# pm2016.net
KiCad netlist of a schematic drawn in EAGLE
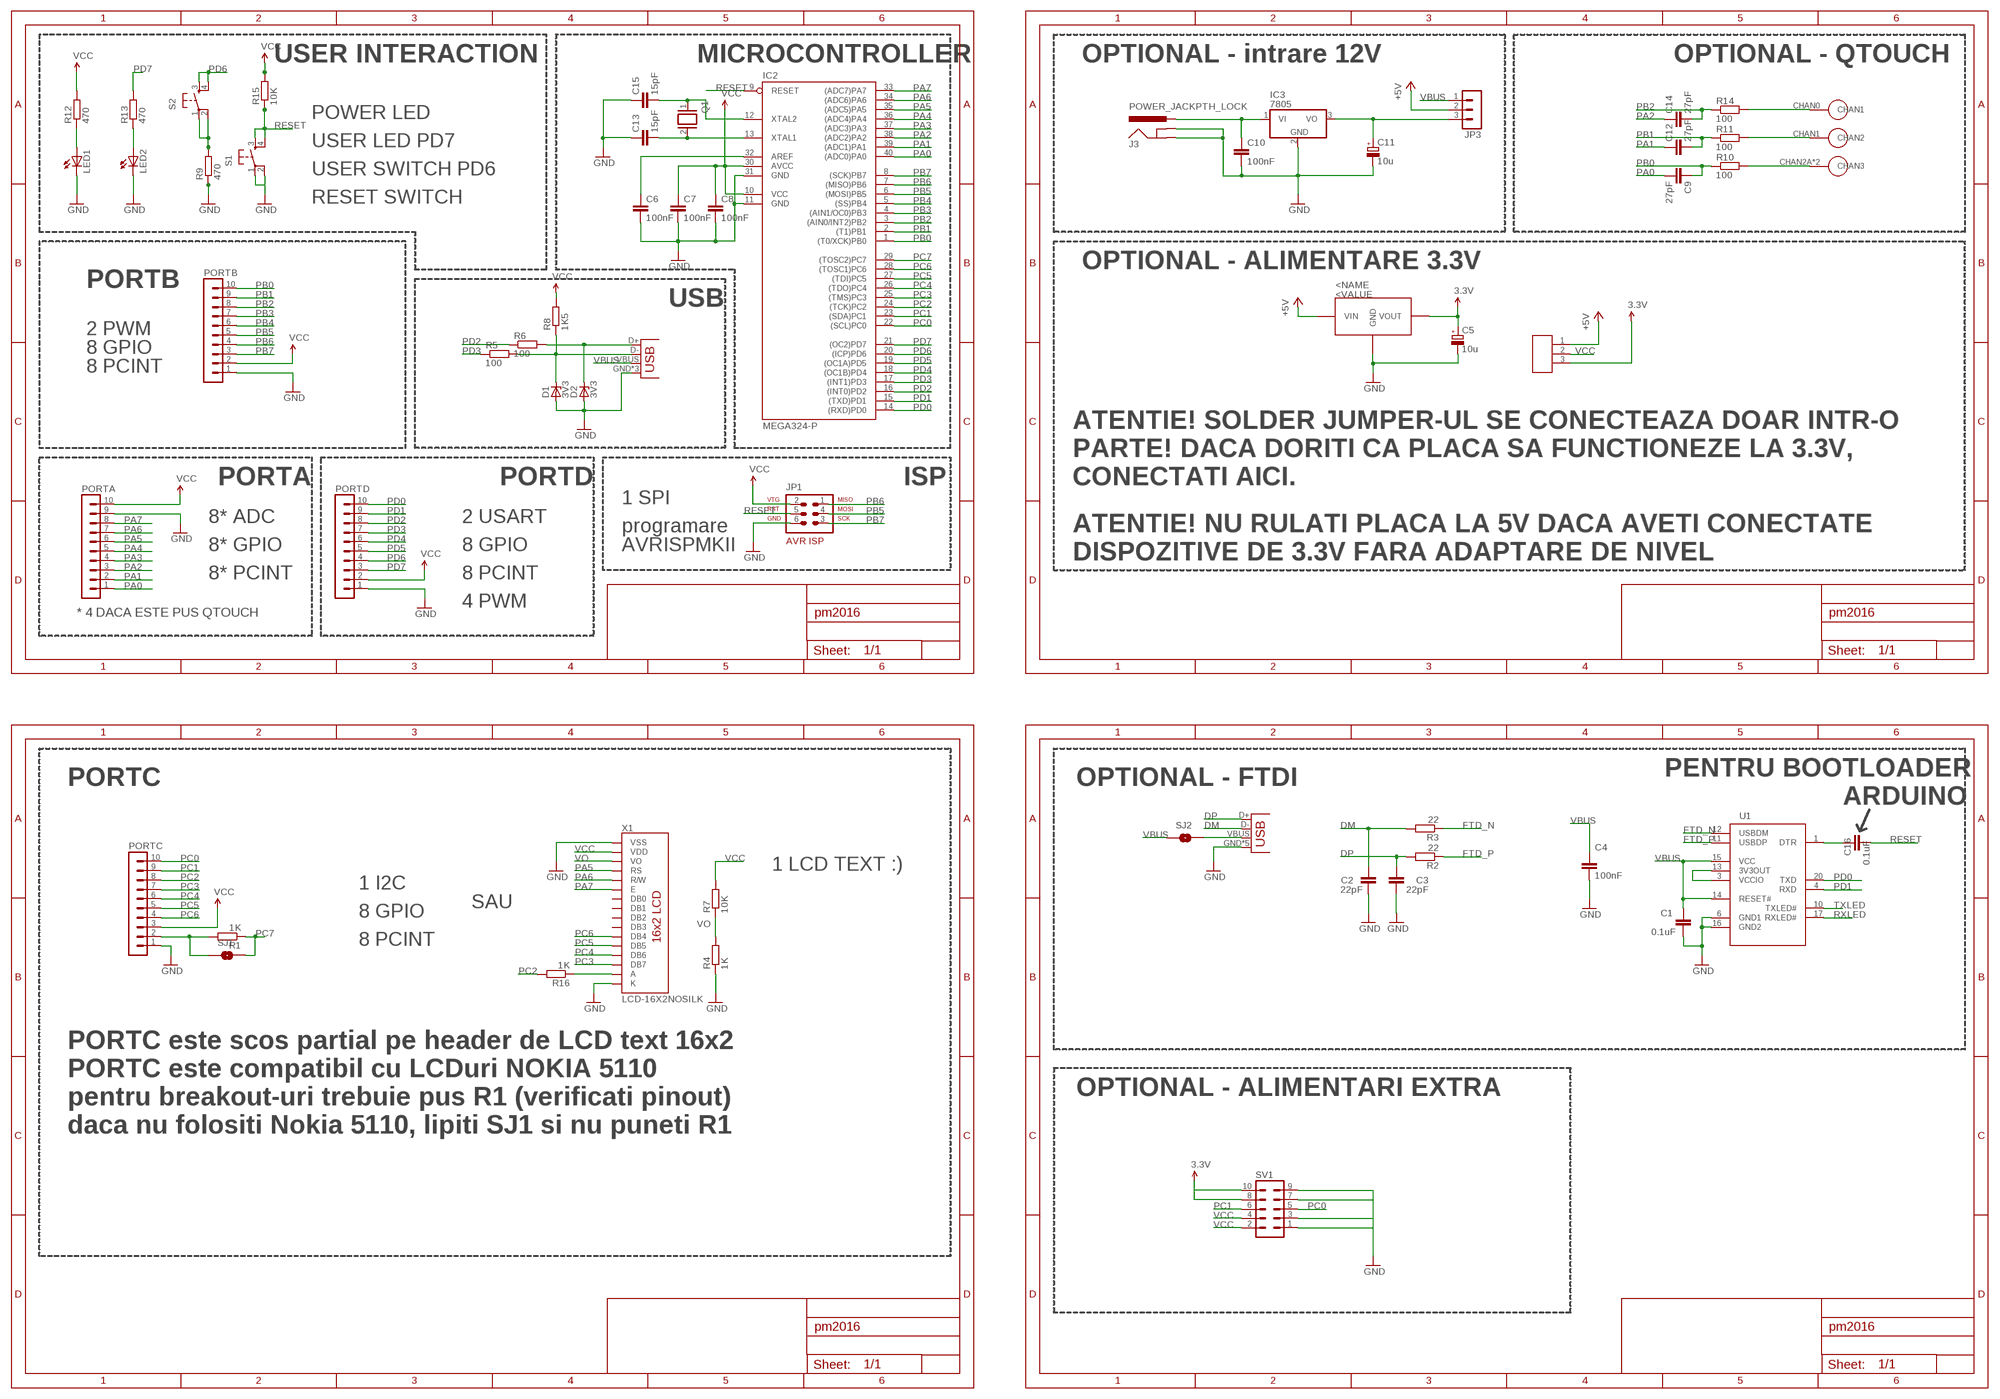
[diagram p0: schematic, sheet 1]

(export (version "E")
  (design (tool "Eeschema 10.0.6"))
  (components
    (comp (ref "C1")
      (value "0.1uF")
      (footprint "eagle-import:C0603")
      (libsource (lib "eagle-import") (part "C-EUC0603"))
    )
    (comp (ref "C2")
      (value "22pF")
      (footprint "eagle-import:C0603")
      (libsource (lib "eagle-import") (part "C-EUC0603"))
    )
    (comp (ref "C3")
      (value "22pF")
      (footprint "eagle-import:C0603")
      (libsource (lib "eagle-import") (part "C-EUC0603"))
    )
    (comp (ref "C4")
      (value "100nF")
      (footprint "eagle-import:C0603")
      (libsource (lib "eagle-import") (part "C-EUC0603"))
    )
    (comp (ref "C5")
      (value "10u")
      (footprint "eagle-import:E2,5-5")
      (libsource (lib "eagle-import") (part "CPOL-EUE2.5-5"))
    )
    (comp (ref "C6")
      (value "100nF")
      (footprint "eagle-import:C025-025X050")
      (libsource (lib "eagle-import") (part "C-EUC_PM"))
    )
    (comp (ref "C7")
      (value "100nF")
      (footprint "eagle-import:C025-025X050")
      (libsource (lib "eagle-import") (part "C-EUC_PM"))
    )
    (comp (ref "C8")
      (value "100nF")
      (footprint "eagle-import:C025-025X050")
      (libsource (lib "eagle-import") (part "C-EUC_PM"))
    )
    (comp (ref "C9")
      (value "27pF")
      (footprint "eagle-import:C1206")
      (libsource (lib "eagle-import") (part "C-EUC1206"))
    )
    (comp (ref "C10")
      (value "100nF")
      (footprint "eagle-import:C025-025X050@1")
      (libsource (lib "eagle-import") (part "C-EU025-025X050"))
    )
    (comp (ref "C11")
      (value "10u")
      (footprint "eagle-import:E2,5-5")
      (libsource (lib "eagle-import") (part "CPOL-EUE2.5-5"))
    )
    (comp (ref "C12")
      (value "27pF")
      (footprint "eagle-import:C1206")
      (libsource (lib "eagle-import") (part "C-EUC1206"))
    )
    (comp (ref "C13")
      (value "15pF")
      (footprint "eagle-import:C025-025X050")
      (libsource (lib "eagle-import") (part "C-EUC_PM"))
    )
    (comp (ref "C14")
      (value "27pF")
      (footprint "eagle-import:C1206")
      (libsource (lib "eagle-import") (part "C-EUC1206"))
    )
    (comp (ref "C15")
      (value "15pF")
      (footprint "eagle-import:C025-025X050")
      (libsource (lib "eagle-import") (part "C-EUC_PM"))
    )
    (comp (ref "C16")
      (value "0.1uF")
      (footprint "eagle-import:C0603")
      (libsource (lib "eagle-import") (part "C-EUC0603"))
    )
    (comp (ref "D1")
      (value "3V3")
      (footprint "eagle-import:DO34Z7")
      (libsource (lib "eagle-import") (part "ZENER-DIODEDO34-7"))
    )
    (comp (ref "D2")
      (value "3V3")
      (footprint "eagle-import:DO34Z7")
      (libsource (lib "eagle-import") (part "ZENER-DIODEDO34-7"))
    )
    (comp (ref "IC1")
      (value "LE33")
      (footprint "eagle-import:TO92")
      (libsource (lib "eagle-import") (part "LE33"))
    )
    (comp (ref "IC2")
      (value "MEGA324-P")
      (footprint "eagle-import:DIL40")
      (fields (field (name "MPN") "ATMEGA16-16PU"))
      (libsource (lib "eagle-import") (part "MEGA16-P"))
    )
    (comp (ref "IC3")
      (value "7805")
      (footprint "eagle-import:TO22H_NOHOLE")
      (libsource (lib "eagle-import") (part "78TNH05"))
    )
    (comp (ref "J1")
      (value "USB")
      (footprint "eagle-import:ZX62D-B-5PA8")
      (libsource (lib "eagle-import") (part "USB"))
    )
    (comp (ref "J2")
      (value "USBPTH")
      (footprint "eagle-import:USB-B-PTH")
      (libsource (lib "eagle-import") (part "USBPTH"))
    )
    (comp (ref "J3")
      (value "POWER_JACKPTH_LOCK")
      (footprint "eagle-import:POWER_JACK_PTH_LOCK")
      (libsource (lib "eagle-import") (part "POWER_JACKPTH_LOCK"))
    )
    (comp (ref "JP1")
      (value "AVR-ISP-6")
      (footprint "eagle-import:AVR-ISP-6")
      (libsource (lib "eagle-import") (part "AVR-ISP-6"))
    )
    (comp (ref "JP2")
      (value "SJUMPER")
      (footprint "eagle-import:SJUMPER_PACK")
      (libsource (lib "eagle-import") (part "SJUMPER"))
    )
    (comp (ref "JP3")
      (value "MA03-1")
      (footprint "eagle-import:MA03-1")
      (libsource (lib "eagle-import") (part "MA03-1"))
    )
    (comp (ref "LED1")
      (value "LED5MM")
      (footprint "eagle-import:LED5MM")
      (libsource (lib "eagle-import") (part "LED5MM"))
    )
    (comp (ref "LED2")
      (value "LED5MM")
      (footprint "eagle-import:LED5MM")
      (libsource (lib "eagle-import") (part "LED5MM"))
    )
    (comp (ref "PORTA")
      (value "MA10-1")
      (footprint "eagle-import:MA10-1")
      (libsource (lib "eagle-import") (part "MA10-1"))
    )
    (comp (ref "PORTB")
      (value "MA10-1")
      (footprint "eagle-import:MA10-1")
      (libsource (lib "eagle-import") (part "MA10-1"))
    )
    (comp (ref "PORTC")
      (value "MA10-1")
      (footprint "eagle-import:MA10-1")
      (libsource (lib "eagle-import") (part "MA10-1"))
    )
    (comp (ref "PORTD")
      (value "MA10-1")
      (footprint "eagle-import:MA10-1")
      (libsource (lib "eagle-import") (part "MA10-1"))
    )
    (comp (ref "Q1")
      (value "XTAL/S")
      (footprint "eagle-import:QS")
      (libsource (lib "eagle-import") (part "XTAL/S"))
    )
    (comp (ref "R1")
      (value "1K")
      (footprint "eagle-import:0204_7")
      (libsource (lib "eagle-import") (part "R-EU_0204/7"))
    )
    (comp (ref "R2")
      (value "22")
      (footprint "eagle-import:R0603")
      (libsource (lib "eagle-import") (part "resistor_R-EU_R0603"))
    )
    (comp (ref "R3")
      (value "22")
      (footprint "eagle-import:R0603")
      (libsource (lib "eagle-import") (part "resistor_R-EU_R0603"))
    )
    (comp (ref "R4")
      (value "1K")
      (footprint "eagle-import:0204_7")
      (libsource (lib "eagle-import") (part "R-EU_0204/7"))
    )
    (comp (ref "R5")
      (value "100")
      (footprint "eagle-import:0204_7")
      (libsource (lib "eagle-import") (part "R-EU_0204/7"))
    )
    (comp (ref "R6")
      (value "100")
      (footprint "eagle-import:0204_7")
      (libsource (lib "eagle-import") (part "R-EU_0204/7"))
    )
    (comp (ref "R7")
      (value "10K")
      (footprint "eagle-import:0204_7")
      (libsource (lib "eagle-import") (part "R-EU_0204/7"))
    )
    (comp (ref "R8")
      (value "1K5")
      (footprint "eagle-import:0204_7")
      (libsource (lib "eagle-import") (part "R-EU_0204/7"))
    )
    (comp (ref "R9")
      (value "470")
      (footprint "eagle-import:0204_7")
      (libsource (lib "eagle-import") (part "R-EU_0204/7"))
    )
    (comp (ref "R10")
      (value "100")
      (footprint "eagle-import:M1206")
      (libsource (lib "eagle-import") (part "resistor_R-EU_M1206"))
    )
    (comp (ref "R11")
      (value "100")
      (footprint "eagle-import:M1206")
      (libsource (lib "eagle-import") (part "resistor_R-EU_M1206"))
    )
    (comp (ref "R12")
      (value "470")
      (footprint "eagle-import:0204_7")
      (libsource (lib "eagle-import") (part "R-EU_0204/7"))
    )
    (comp (ref "R13")
      (value "470")
      (footprint "eagle-import:0204_7")
      (libsource (lib "eagle-import") (part "R-EU_0204/7"))
    )
    (comp (ref "R14")
      (value "100")
      (footprint "eagle-import:M1206")
      (libsource (lib "eagle-import") (part "resistor_R-EU_M1206"))
    )
    (comp (ref "R15")
      (value "10K")
      (footprint "eagle-import:0204_7")
      (libsource (lib "eagle-import") (part "R-EU_0204/7"))
    )
    (comp (ref "R16")
      (value "1K")
      (footprint "eagle-import:0204_7")
      (libsource (lib "eagle-import") (part "R-EU_0204/7"))
    )
    (comp (ref "S1")
      (value "TAC_SWITCHPTH")
      (footprint "eagle-import:TACTILE-PTH")
      (libsource (lib "eagle-import") (part "TAC_SWITCHPTH"))
    )
    (comp (ref "S2")
      (value "TAC_SWITCHPTH")
      (footprint "eagle-import:TACTILE-PTH")
      (libsource (lib "eagle-import") (part "TAC_SWITCHPTH"))
    )
    (comp (ref "SJ1")
      (value "SOLDERJUMPERNC")
      (footprint "eagle-import:SJ-NC")
      (libsource (lib "eagle-import") (part "SOLDERJUMPERNC"))
    )
    (comp (ref "SJ2")
      (value "SOLDERJUMPERNC")
      (footprint "eagle-import:SJ-NC")
      (libsource (lib "eagle-import") (part "SOLDERJUMPERNC"))
    )
    (comp (ref "SV1")
      (value "MA05-2")
      (footprint "eagle-import:MA05-2")
      (libsource (lib "eagle-import") (part "MA05-2"))
    )
    (comp (ref "U$1")
      (value "QT_SLIDER")
      (footprint "eagle-import:QT_SLIDER")
      (libsource (lib "eagle-import") (part "QT_SLIDER"))
    )
    (comp (ref "U1")
      (value "FT231XS")
      (footprint "eagle-import:SSOP20")
      (libsource (lib "eagle-import") (part "FT231XS"))
    )
    (comp (ref "X1")
      (value "LCD-16X2NOSILK")
      (footprint "eagle-import:LCD-16X2_NOSILK")
      (libsource (lib "eagle-import") (part "LCD-16X2NOSILK"))
    )
  )
  (nets
    (net (code "1") (name "+5V") (class "Default")
      (node (ref "IC1") (pin "3") (pinfunction "VIN_3") (pintype "bidirectional"))
      (node (ref "JP2") (pin "1") (pinfunction "P$1_1") (pintype "bidirectional"))
      (node (ref "JP3") (pin "2") (pinfunction "2_2") (pintype "passive"))
    )
    (net (code "2") (name "/DM") (class "Default")
      (node (ref "C2") (pin "2") (pinfunction "2_2") (pintype "passive"))
      (node (ref "J1") (pin "D-") (pinfunction "D-_D-") (pintype "bidirectional"))
      (node (ref "R3") (pin "2") (pinfunction "2_2") (pintype "passive"))
    )
    (net (code "3") (name "/DP") (class "Default")
      (node (ref "C3") (pin "2") (pinfunction "2_2") (pintype "passive"))
      (node (ref "J1") (pin "D+") (pinfunction "D+_D+") (pintype "bidirectional"))
      (node (ref "R2") (pin "2") (pinfunction "2_2") (pintype "passive"))
    )
    (net (code "4") (name "/FTD_N") (class "Default")
      (node (ref "R3") (pin "1") (pinfunction "1_1") (pintype "passive"))
      (node (ref "U1") (pin "12") (pinfunction "USBDM_12") (pintype "bidirectional"))
    )
    (net (code "5") (name "/FTD_P") (class "Default")
      (node (ref "R2") (pin "1") (pinfunction "1_1") (pintype "passive"))
      (node (ref "U1") (pin "11") (pinfunction "USBDP_11") (pintype "bidirectional"))
    )
    (net (code "6") (name "/PA0") (class "Default")
      (node (ref "C9") (pin "2") (pinfunction "2_2") (pintype "passive"))
      (node (ref "IC2") (pin "40") (pinfunction "(ADC0)PA0_40") (pintype "bidirectional"))
      (node (ref "PORTA") (pin "1") (pinfunction "1_1") (pintype "passive"))
    )
    (net (code "7") (name "/PA1") (class "Default")
      (node (ref "C12") (pin "1") (pinfunction "1_1") (pintype "passive"))
      (node (ref "IC2") (pin "39") (pinfunction "(ADC1)PA1_39") (pintype "bidirectional"))
      (node (ref "PORTA") (pin "2") (pinfunction "2_2") (pintype "passive"))
    )
    (net (code "8") (name "/PA2") (class "Default")
      (node (ref "C14") (pin "1") (pinfunction "1_1") (pintype "passive"))
      (node (ref "IC2") (pin "38") (pinfunction "(ADC2)PA2_38") (pintype "bidirectional"))
      (node (ref "PORTA") (pin "3") (pinfunction "3_3") (pintype "passive"))
    )
    (net (code "9") (name "/PA3") (class "Default")
      (node (ref "IC2") (pin "37") (pinfunction "(ADC3)PA3_37") (pintype "bidirectional"))
      (node (ref "PORTA") (pin "4") (pinfunction "4_4") (pintype "passive"))
    )
    (net (code "10") (name "/PA4") (class "Default")
      (node (ref "IC2") (pin "36") (pinfunction "(ADC4)PA4_36") (pintype "bidirectional"))
      (node (ref "PORTA") (pin "5") (pinfunction "5_5") (pintype "passive"))
    )
    (net (code "11") (name "/PA5") (class "Default")
      (node (ref "IC2") (pin "35") (pinfunction "(ADC5)PA5_35") (pintype "bidirectional"))
      (node (ref "PORTA") (pin "6") (pinfunction "6_6") (pintype "passive"))
      (node (ref "X1") (pin "4") (pinfunction "RS_4") (pintype "input"))
    )
    (net (code "12") (name "/PA6") (class "Default")
      (node (ref "IC2") (pin "34") (pinfunction "(ADC6)PA6_34") (pintype "bidirectional"))
      (node (ref "PORTA") (pin "7") (pinfunction "7_7") (pintype "passive"))
      (node (ref "X1") (pin "5") (pinfunction "R/W_5") (pintype "input"))
    )
    (net (code "13") (name "/PA7") (class "Default")
      (node (ref "IC2") (pin "33") (pinfunction "(ADC7)PA7_33") (pintype "bidirectional"))
      (node (ref "PORTA") (pin "8") (pinfunction "8_8") (pintype "passive"))
      (node (ref "X1") (pin "6") (pinfunction "E_6") (pintype "input"))
    )
    (net (code "14") (name "/PB0") (class "Default")
      (node (ref "C9") (pin "1") (pinfunction "1_1") (pintype "passive"))
      (node (ref "IC2") (pin "1") (pinfunction "(T0/XCK)PB0_1") (pintype "bidirectional"))
      (node (ref "PORTB") (pin "10") (pinfunction "10_10") (pintype "passive"))
      (node (ref "R10") (pin "1") (pinfunction "1_1") (pintype "passive"))
    )
    (net (code "15") (name "/PB1") (class "Default")
      (node (ref "C12") (pin "2") (pinfunction "2_2") (pintype "passive"))
      (node (ref "IC2") (pin "2") (pinfunction "(T1)PB1_2") (pintype "bidirectional"))
      (node (ref "PORTB") (pin "9") (pinfunction "9_9") (pintype "passive"))
      (node (ref "R11") (pin "1") (pinfunction "1_1") (pintype "passive"))
    )
    (net (code "16") (name "/PB2") (class "Default")
      (node (ref "C14") (pin "2") (pinfunction "2_2") (pintype "passive"))
      (node (ref "IC2") (pin "3") (pinfunction "(AIN0/INT2)PB2_3") (pintype "bidirectional"))
      (node (ref "PORTB") (pin "8") (pinfunction "8_8") (pintype "passive"))
      (node (ref "R14") (pin "1") (pinfunction "1_1") (pintype "passive"))
    )
    (net (code "17") (name "/PB3") (class "Default")
      (node (ref "IC2") (pin "4") (pinfunction "(AIN1/OC0)PB3_4") (pintype "bidirectional"))
      (node (ref "PORTB") (pin "7") (pinfunction "7_7") (pintype "passive"))
    )
    (net (code "18") (name "/PB4") (class "Default")
      (node (ref "IC2") (pin "5") (pinfunction "(SS)PB4_5") (pintype "bidirectional"))
      (node (ref "PORTB") (pin "6") (pinfunction "6_6") (pintype "passive"))
    )
    (net (code "19") (name "/PB5") (class "Default")
      (node (ref "IC2") (pin "6") (pinfunction "(MOSI)PB5_6") (pintype "bidirectional"))
      (node (ref "JP1") (pin "4") (pinfunction "4_4") (pintype "passive"))
      (node (ref "PORTB") (pin "5") (pinfunction "5_5") (pintype "passive"))
    )
    (net (code "20") (name "/PB6") (class "Default")
      (node (ref "IC2") (pin "7") (pinfunction "(MISO)PB6_7") (pintype "bidirectional"))
      (node (ref "JP1") (pin "1") (pinfunction "1_1") (pintype "passive"))
      (node (ref "PORTB") (pin "4") (pinfunction "4_4") (pintype "passive"))
    )
    (net (code "21") (name "/PB7") (class "Default")
      (node (ref "IC2") (pin "8") (pinfunction "(SCK)PB7_8") (pintype "bidirectional"))
      (node (ref "JP1") (pin "3") (pinfunction "3_3") (pintype "passive"))
      (node (ref "PORTB") (pin "3") (pinfunction "3_3") (pintype "passive"))
    )
    (net (code "22") (name "/PC0") (class "Default")
      (node (ref "IC2") (pin "22") (pinfunction "(SCL)PC0_22") (pintype "bidirectional"))
      (node (ref "PORTC") (pin "10") (pinfunction "10_10") (pintype "passive"))
      (node (ref "SV1") (pin "5") (pinfunction "5_5") (pintype "passive"))
    )
    (net (code "23") (name "/PC1") (class "Default")
      (node (ref "IC2") (pin "23") (pinfunction "(SDA)PC1_23") (pintype "bidirectional"))
      (node (ref "PORTC") (pin "9") (pinfunction "9_9") (pintype "passive"))
      (node (ref "SV1") (pin "6") (pinfunction "6_6") (pintype "passive"))
    )
    (net (code "24") (name "/PC2") (class "Default")
      (node (ref "IC2") (pin "24") (pinfunction "(TCK)PC2_24") (pintype "bidirectional"))
      (node (ref "PORTC") (pin "8") (pinfunction "8_8") (pintype "passive"))
      (node (ref "R16") (pin "2") (pinfunction "2_2") (pintype "passive"))
    )
    (net (code "25") (name "/PC3") (class "Default")
      (node (ref "IC2") (pin "25") (pinfunction "(TMS)PC3_25") (pintype "bidirectional"))
      (node (ref "PORTC") (pin "7") (pinfunction "7_7") (pintype "passive"))
      (node (ref "X1") (pin "14") (pinfunction "DB7_14") (pintype "bidirectional"))
    )
    (net (code "26") (name "/PC4") (class "Default")
      (node (ref "IC2") (pin "26") (pinfunction "(TDO)PC4_26") (pintype "bidirectional"))
      (node (ref "PORTC") (pin "6") (pinfunction "6_6") (pintype "passive"))
      (node (ref "X1") (pin "13") (pinfunction "DB6_13") (pintype "bidirectional"))
    )
    (net (code "27") (name "/PC5") (class "Default")
      (node (ref "IC2") (pin "27") (pinfunction "(TDI)PC5_27") (pintype "bidirectional"))
      (node (ref "PORTC") (pin "5") (pinfunction "5_5") (pintype "passive"))
      (node (ref "X1") (pin "12") (pinfunction "DB5_12") (pintype "bidirectional"))
    )
    (net (code "28") (name "/PC6") (class "Default")
      (node (ref "IC2") (pin "28") (pinfunction "(TOSC1)PC6_28") (pintype "bidirectional"))
      (node (ref "PORTC") (pin "4") (pinfunction "4_4") (pintype "passive"))
      (node (ref "X1") (pin "11") (pinfunction "DB4_11") (pintype "bidirectional"))
    )
    (net (code "29") (name "/PC7") (class "Default")
      (node (ref "IC2") (pin "29") (pinfunction "(TOSC2)PC7_29") (pintype "bidirectional"))
      (node (ref "R1") (pin "1") (pinfunction "1_1") (pintype "passive"))
      (node (ref "SJ1") (pin "2") (pinfunction "2_2") (pintype "passive"))
    )
    (net (code "30") (name "/PD0") (class "Default")
      (node (ref "IC2") (pin "14") (pinfunction "(RXD)PD0_14") (pintype "bidirectional"))
      (node (ref "PORTD") (pin "10") (pinfunction "10_10") (pintype "passive"))
      (node (ref "U1") (pin "20") (pinfunction "TXD_20") (pintype "output"))
    )
    (net (code "31") (name "/PD1") (class "Default")
      (node (ref "IC2") (pin "15") (pinfunction "(TXD)PD1_15") (pintype "bidirectional"))
      (node (ref "PORTD") (pin "9") (pinfunction "9_9") (pintype "passive"))
      (node (ref "U1") (pin "4") (pinfunction "RXD_4") (pintype "input"))
    )
    (net (code "32") (name "/PD2") (class "Default")
      (node (ref "IC2") (pin "16") (pinfunction "(INT0)PD2_16") (pintype "bidirectional"))
      (node (ref "PORTD") (pin "8") (pinfunction "8_8") (pintype "passive"))
      (node (ref "R6") (pin "1") (pinfunction "1_1") (pintype "passive"))
    )
    (net (code "33") (name "/PD3") (class "Default")
      (node (ref "IC2") (pin "17") (pinfunction "(INT1)PD3_17") (pintype "bidirectional"))
      (node (ref "PORTD") (pin "7") (pinfunction "7_7") (pintype "passive"))
      (node (ref "R5") (pin "1") (pinfunction "1_1") (pintype "passive"))
    )
    (net (code "34") (name "/PD4") (class "Default")
      (node (ref "IC2") (pin "18") (pinfunction "(OC1B)PD4_18") (pintype "bidirectional"))
      (node (ref "PORTD") (pin "6") (pinfunction "6_6") (pintype "passive"))
    )
    (net (code "35") (name "/PD5") (class "Default")
      (node (ref "IC2") (pin "19") (pinfunction "(OC1A)PD5_19") (pintype "bidirectional"))
      (node (ref "PORTD") (pin "5") (pinfunction "5_5") (pintype "passive"))
    )
    (net (code "36") (name "/PD6") (class "Default")
      (node (ref "IC2") (pin "20") (pinfunction "(ICP)PD6_20") (pintype "bidirectional"))
      (node (ref "PORTD") (pin "4") (pinfunction "4_4") (pintype "passive"))
      (node (ref "S2") (pin "3") (pinfunction "3_3") (pintype "passive"))
      (node (ref "S2") (pin "4") (pinfunction "4_4") (pintype "passive"))
    )
    (net (code "37") (name "/PD7") (class "Default")
      (node (ref "IC2") (pin "21") (pinfunction "(OC2)PD7_21") (pintype "bidirectional"))
      (node (ref "PORTD") (pin "3") (pinfunction "3_3") (pintype "passive"))
      (node (ref "R13") (pin "2") (pinfunction "2_2") (pintype "passive"))
    )
    (net (code "38") (name "/RESET") (class "Default")
      (node (ref "C16") (pin "2") (pinfunction "2_2") (pintype "passive"))
      (node (ref "IC2") (pin "9") (pinfunction "RESET_9") (pintype "input"))
      (node (ref "JP1") (pin "5") (pinfunction "5_5") (pintype "passive"))
      (node (ref "R15") (pin "1") (pinfunction "1_1") (pintype "passive"))
      (node (ref "S1") (pin "3") (pinfunction "3_3") (pintype "passive"))
      (node (ref "S1") (pin "4") (pinfunction "4_4") (pintype "passive"))
    )
    (net (code "39") (name "/RXLED") (class "Default")
      (node (ref "U1") (pin "17") (pinfunction "RXLED#_17") (pintype "output"))
    )
    (net (code "40") (name "/TXLED") (class "Default")
      (node (ref "U1") (pin "10") (pinfunction "TXLED#_10") (pintype "output"))
    )
    (net (code "41") (name "/VBUS") (class "Default")
      (node (ref "C1") (pin "1") (pinfunction "1_1") (pintype "passive"))
      (node (ref "C4") (pin "1") (pinfunction "1_1") (pintype "passive"))
      (node (ref "J2") (pin "VBUS") (pinfunction "VBUS_VBUS") (pintype "bidirectional"))
      (node (ref "JP3") (pin "1") (pinfunction "1_1") (pintype "passive"))
      (node (ref "SJ2") (pin "1") (pinfunction "1_1") (pintype "passive"))
      (node (ref "U1") (pin "14") (pinfunction "RESET#_14") (pintype "input"))
      (node (ref "U1") (pin "15") (pinfunction "VCC_15") (pintype "power_in"))
    )
    (net (code "42") (name "/VO") (class "Default")
      (node (ref "R4") (pin "2") (pinfunction "2_2") (pintype "passive"))
      (node (ref "R7") (pin "1") (pinfunction "1_1") (pintype "passive"))
      (node (ref "X1") (pin "3") (pinfunction "VO_3") (pintype "bidirectional"))
    )
    (net (code "43") (name "3.3V") (class "Default")
      (node (ref "C5") (pin "+") (pinfunction "+_+") (pintype "passive"))
      (node (ref "IC1") (pin "1") (pinfunction "VOUT_1") (pintype "bidirectional"))
      (node (ref "JP2") (pin "3") (pinfunction "P$3_3") (pintype "bidirectional"))
      (node (ref "SV1") (pin "10") (pinfunction "10_10") (pintype "passive"))
      (node (ref "SV1") (pin "8") (pinfunction "8_8") (pintype "passive"))
    )
    (net (code "44") (name "GND") (class "Default")
      (node (ref "C1") (pin "2") (pinfunction "2_2") (pintype "passive"))
      (node (ref "C10") (pin "2") (pinfunction "2_2") (pintype "passive"))
      (node (ref "C11") (pin "-") (pinfunction "-_-") (pintype "passive"))
      (node (ref "C13") (pin "1") (pinfunction "1_1") (pintype "passive"))
      (node (ref "C15") (pin "1") (pinfunction "1_1") (pintype "passive"))
      (node (ref "C2") (pin "1") (pinfunction "1_1") (pintype "passive"))
      (node (ref "C3") (pin "1") (pinfunction "1_1") (pintype "passive"))
      (node (ref "C4") (pin "2") (pinfunction "2_2") (pintype "passive"))
      (node (ref "C5") (pin "-") (pinfunction "-_-") (pintype "passive"))
      (node (ref "C6") (pin "2") (pinfunction "2_2") (pintype "passive"))
      (node (ref "C7") (pin "2") (pinfunction "2_2") (pintype "passive"))
      (node (ref "C8") (pin "2") (pinfunction "2_2") (pintype "passive"))
      (node (ref "D1") (pin "A") (pinfunction "A_A") (pintype "passive"))
      (node (ref "D2") (pin "A") (pinfunction "A_A") (pintype "passive"))
      (node (ref "IC1") (pin "2") (pinfunction "GND_2") (pintype "bidirectional"))
      (node (ref "IC2") (pin "11") (pinfunction "GND_11") (pintype "power_in"))
      (node (ref "IC2") (pin "31") (pinfunction "GND_31") (pintype "power_in"))
      (node (ref "IC3") (pin "2") (pinfunction "GND_2") (pintype "passive"))
      (node (ref "J1") (pin "GND") (pinfunction "GND_GND") (pintype "bidirectional"))
      (node (ref "J1") (pin "P$10") (pinfunction "GND_P$10") (pintype "bidirectional"))
      (node (ref "J1") (pin "P$11") (pinfunction "GND_P$11") (pintype "bidirectional"))
      (node (ref "J1") (pin "P$8") (pinfunction "GND_P$8") (pintype "bidirectional"))
      (node (ref "J1") (pin "P$9") (pinfunction "GND_P$9") (pintype "bidirectional"))
      (node (ref "J2") (pin "GND") (pinfunction "GND_GND") (pintype "bidirectional"))
      (node (ref "J2") (pin "P$1") (pinfunction "GND_P$1") (pintype "bidirectional"))
      (node (ref "J2") (pin "P$2") (pinfunction "GND_P$2") (pintype "bidirectional"))
      (node (ref "J3") (pin "GND") (pinfunction "GND_GND") (pintype "bidirectional"))
      (node (ref "J3") (pin "GNDBREAK") (pinfunction "GNDBREAK_GNDBREAK") (pintype "bidirectional"))
      (node (ref "JP1") (pin "6") (pinfunction "6_6") (pintype "passive"))
      (node (ref "LED1") (pin "K") (pinfunction "C_K") (pintype "passive"))
      (node (ref "LED2") (pin "K") (pinfunction "C_K") (pintype "passive"))
      (node (ref "PORTA") (pin "9") (pinfunction "9_9") (pintype "passive"))
      (node (ref "PORTB") (pin "1") (pinfunction "1_1") (pintype "passive"))
      (node (ref "PORTC") (pin "1") (pinfunction "1_1") (pintype "passive"))
      (node (ref "PORTD") (pin "1") (pinfunction "1_1") (pintype "passive"))
      (node (ref "R4") (pin "1") (pinfunction "1_1") (pintype "passive"))
      (node (ref "R9") (pin "1") (pinfunction "1_1") (pintype "passive"))
      (node (ref "S1") (pin "1") (pinfunction "1_1") (pintype "passive"))
      (node (ref "S1") (pin "2") (pinfunction "2_2") (pintype "passive"))
      (node (ref "SV1") (pin "1") (pinfunction "1_1") (pintype "passive"))
      (node (ref "SV1") (pin "3") (pinfunction "3_3") (pintype "passive"))
      (node (ref "SV1") (pin "7") (pinfunction "7_7") (pintype "passive"))
      (node (ref "SV1") (pin "9") (pinfunction "9_9") (pintype "passive"))
      (node (ref "U1") (pin "16") (pinfunction "GND2_16") (pintype "power_in"))
      (node (ref "U1") (pin "6") (pinfunction "GND1_6") (pintype "power_in"))
      (node (ref "X1") (pin "1") (pinfunction "VSS_1") (pintype "power_in"))
      (node (ref "X1") (pin "16") (pinfunction "K_16") (pintype "power_in"))
    )
    (net (code "45") (name "Net-(D1-PadC)") (class "Default")
      (node (ref "D1") (pin "C") (pinfunction "C_C") (pintype "passive"))
      (node (ref "J2") (pin "D-") (pinfunction "D-_D-") (pintype "bidirectional"))
      (node (ref "R5") (pin "2") (pinfunction "2_2") (pintype "passive"))
      (node (ref "R8") (pin "1") (pinfunction "1_1") (pintype "passive"))
    )
    (net (code "46") (name "Net-(D2-PadC)") (class "Default")
      (node (ref "D2") (pin "C") (pinfunction "C_C") (pintype "passive"))
      (node (ref "J2") (pin "D+") (pinfunction "D+_D+") (pintype "bidirectional"))
      (node (ref "R6") (pin "2") (pinfunction "2_2") (pintype "passive"))
    )
    (net (code "47") (name "Net-(IC2-AREF)") (class "Default")
      (node (ref "C6") (pin "1") (pinfunction "1_1") (pintype "passive"))
      (node (ref "IC2") (pin "32") (pinfunction "AREF_32") (pintype "passive"))
    )
    (net (code "48") (name "Net-(IC2-XTAL1)") (class "Default")
      (node (ref "C13") (pin "2") (pinfunction "2_2") (pintype "passive"))
      (node (ref "IC2") (pin "13") (pinfunction "XTAL1_13") (pintype "bidirectional"))
      (node (ref "Q1") (pin "2") (pinfunction "2_2") (pintype "passive"))
    )
    (net (code "49") (name "Net-(IC2-XTAL2)") (class "Default")
      (node (ref "C15") (pin "2") (pinfunction "2_2") (pintype "passive"))
      (node (ref "IC2") (pin "12") (pinfunction "XTAL2_12") (pintype "bidirectional"))
      (node (ref "Q1") (pin "1") (pinfunction "1_1") (pintype "passive"))
    )
    (net (code "50") (name "Net-(IC3-VI)") (class "Default")
      (node (ref "C10") (pin "1") (pinfunction "1_1") (pintype "passive"))
      (node (ref "IC3") (pin "1") (pinfunction "VI_1") (pintype "input"))
      (node (ref "J3") (pin "PWR") (pinfunction "PWR_PWR") (pintype "bidirectional"))
    )
    (net (code "51") (name "Net-(IC3-VO)") (class "Default")
      (node (ref "C11") (pin "+") (pinfunction "+_+") (pintype "passive"))
      (node (ref "IC3") (pin "3") (pinfunction "VO_3") (pintype "passive"))
      (node (ref "JP3") (pin "3") (pinfunction "3_3") (pintype "passive"))
    )
    (net (code "52") (name "Net-(J1-PadVBUS)") (class "Default")
      (node (ref "J1") (pin "VBUS") (pinfunction "VBUS_VBUS") (pintype "bidirectional"))
      (node (ref "SJ2") (pin "2") (pinfunction "2_2") (pintype "passive"))
    )
    (net (code "53") (name "Net-(LED1-PadA)") (class "Default")
      (node (ref "LED1") (pin "A") (pinfunction "A_A") (pintype "passive"))
      (node (ref "R12") (pin "1") (pinfunction "1_1") (pintype "passive"))
    )
    (net (code "54") (name "Net-(LED2-PadA)") (class "Default")
      (node (ref "LED2") (pin "A") (pinfunction "A_A") (pintype "passive"))
      (node (ref "R13") (pin "1") (pinfunction "1_1") (pintype "passive"))
    )
    (net (code "55") (name "Net-(PORTC-Pad2)") (class "Default")
      (node (ref "PORTC") (pin "2") (pinfunction "2_2") (pintype "passive"))
      (node (ref "R1") (pin "2") (pinfunction "2_2") (pintype "passive"))
      (node (ref "SJ1") (pin "1") (pinfunction "1_1") (pintype "passive"))
    )
    (net (code "56") (name "Net-(R9-Pad2)") (class "Default")
      (node (ref "R9") (pin "2") (pinfunction "2_2") (pintype "passive"))
      (node (ref "S2") (pin "1") (pinfunction "1_1") (pintype "passive"))
      (node (ref "S2") (pin "2") (pinfunction "2_2") (pintype "passive"))
    )
    (net (code "57") (name "Net-(R10-Pad2)") (class "Default")
      (node (ref "R10") (pin "2") (pinfunction "2_2") (pintype "passive"))
      (node (ref "U$1") (pin "CHAN2A") (pinfunction "CHAN3_CHAN2A") (pintype "bidirectional"))
      (node (ref "U$1") (pin "CHAN2B") (pinfunction "CHAN3_CHAN2B") (pintype "bidirectional"))
    )
    (net (code "58") (name "Net-(U$1-CHAN1)") (class "Default")
      (node (ref "R14") (pin "2") (pinfunction "2_2") (pintype "passive"))
      (node (ref "U$1") (pin "CHAN0") (pinfunction "CHAN1_CHAN0") (pintype "bidirectional"))
    )
    (net (code "59") (name "Net-(U$1-CHAN2)") (class "Default")
      (node (ref "R11") (pin "2") (pinfunction "2_2") (pintype "passive"))
      (node (ref "U$1") (pin "CHAN1") (pinfunction "CHAN2_CHAN1") (pintype "bidirectional"))
    )
    (net (code "60") (name "Net-(U1-3V3OUT)") (class "Default")
      (node (ref "U1") (pin "13") (pinfunction "3V3OUT_13") (pintype "output"))
      (node (ref "U1") (pin "3") (pinfunction "VCCIO_3") (pintype "power_in"))
    )
    (net (code "61") (name "Net-(U1-DTR)") (class "Default")
      (node (ref "C16") (pin "1") (pinfunction "1_1") (pintype "passive"))
      (node (ref "U1") (pin "1") (pinfunction "DTR_1") (pintype "bidirectional"))
    )
    (net (code "62") (name "Net-(X1-A)") (class "Default")
      (node (ref "R16") (pin "1") (pinfunction "1_1") (pintype "passive"))
      (node (ref "X1") (pin "15") (pinfunction "A_15") (pintype "power_in"))
    )
    (net (code "63") (name "VCC") (class "Default")
      (node (ref "C7") (pin "1") (pinfunction "1_1") (pintype "passive"))
      (node (ref "C8") (pin "1") (pinfunction "1_1") (pintype "passive"))
      (node (ref "IC2") (pin "10") (pinfunction "VCC_10") (pintype "power_in"))
      (node (ref "IC2") (pin "30") (pinfunction "AVCC_30") (pintype "power_in"))
      (node (ref "JP1") (pin "2") (pinfunction "2_2") (pintype "passive"))
      (node (ref "JP2") (pin "2") (pinfunction "P$2_2") (pintype "bidirectional"))
      (node (ref "PORTA") (pin "10") (pinfunction "10_10") (pintype "passive"))
      (node (ref "PORTB") (pin "2") (pinfunction "2_2") (pintype "passive"))
      (node (ref "PORTC") (pin "3") (pinfunction "3_3") (pintype "passive"))
      (node (ref "PORTD") (pin "2") (pinfunction "2_2") (pintype "passive"))
      (node (ref "R12") (pin "2") (pinfunction "2_2") (pintype "passive"))
      (node (ref "R15") (pin "2") (pinfunction "2_2") (pintype "passive"))
      (node (ref "R7") (pin "2") (pinfunction "2_2") (pintype "passive"))
      (node (ref "R8") (pin "2") (pinfunction "2_2") (pintype "passive"))
      (node (ref "SV1") (pin "2") (pinfunction "2_2") (pintype "passive"))
      (node (ref "SV1") (pin "4") (pinfunction "4_4") (pintype "passive"))
      (node (ref "X1") (pin "2") (pinfunction "VDD_2") (pintype "power_in"))
    )
    (net (code "64") (name "unconnected-(X1-DB0-Pad7)") (class "Default")
      (node (ref "X1") (pin "7") (pinfunction "DB0_7") (pintype "bidirectional"))
    )
    (net (code "65") (name "unconnected-(X1-DB1-Pad8)") (class "Default")
      (node (ref "X1") (pin "8") (pinfunction "DB1_8") (pintype "bidirectional"))
    )
    (net (code "66") (name "unconnected-(X1-DB2-Pad9)") (class "Default")
      (node (ref "X1") (pin "9") (pinfunction "DB2_9") (pintype "bidirectional"))
    )
    (net (code "67") (name "unconnected-(X1-DB3-Pad10)") (class "Default")
      (node (ref "X1") (pin "10") (pinfunction "DB3_10") (pintype "bidirectional"))
    )
  )
)
